# PicoPrint-Motors.net
KiCad netlist of a schematic drawn in Altium Designer
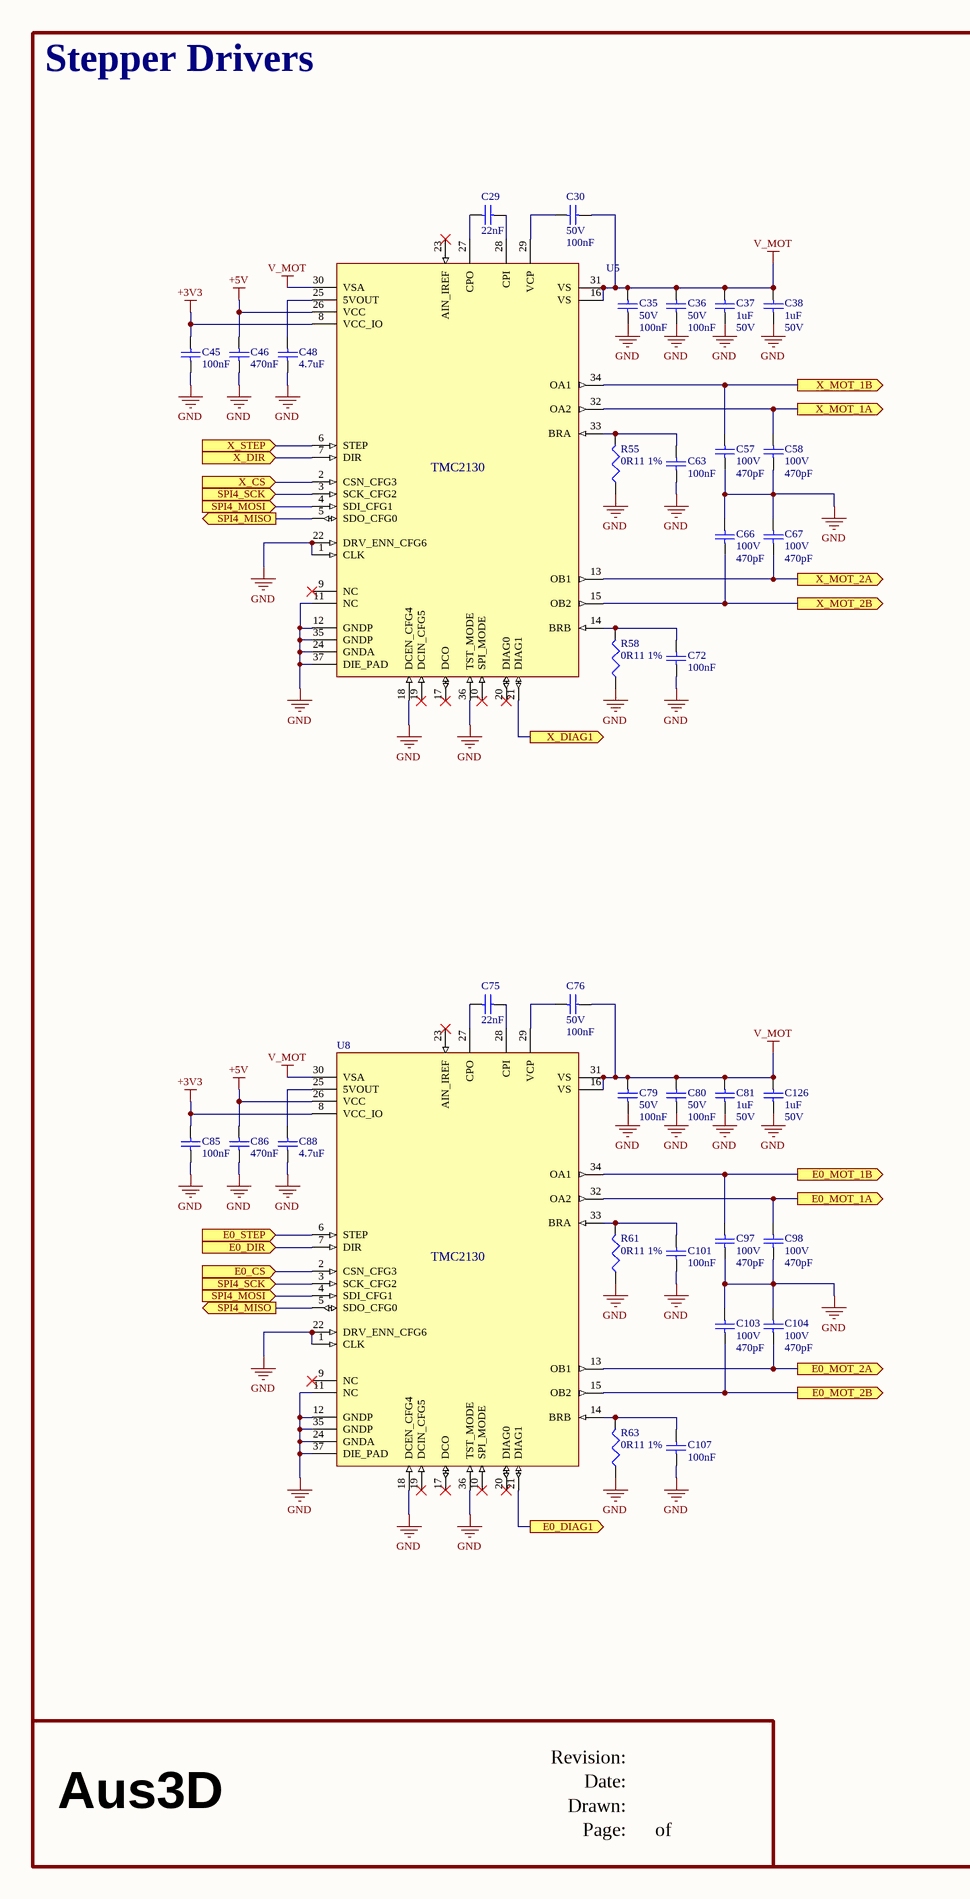
[diagram p0: PicoPrint-Motors.SchDoc, left]
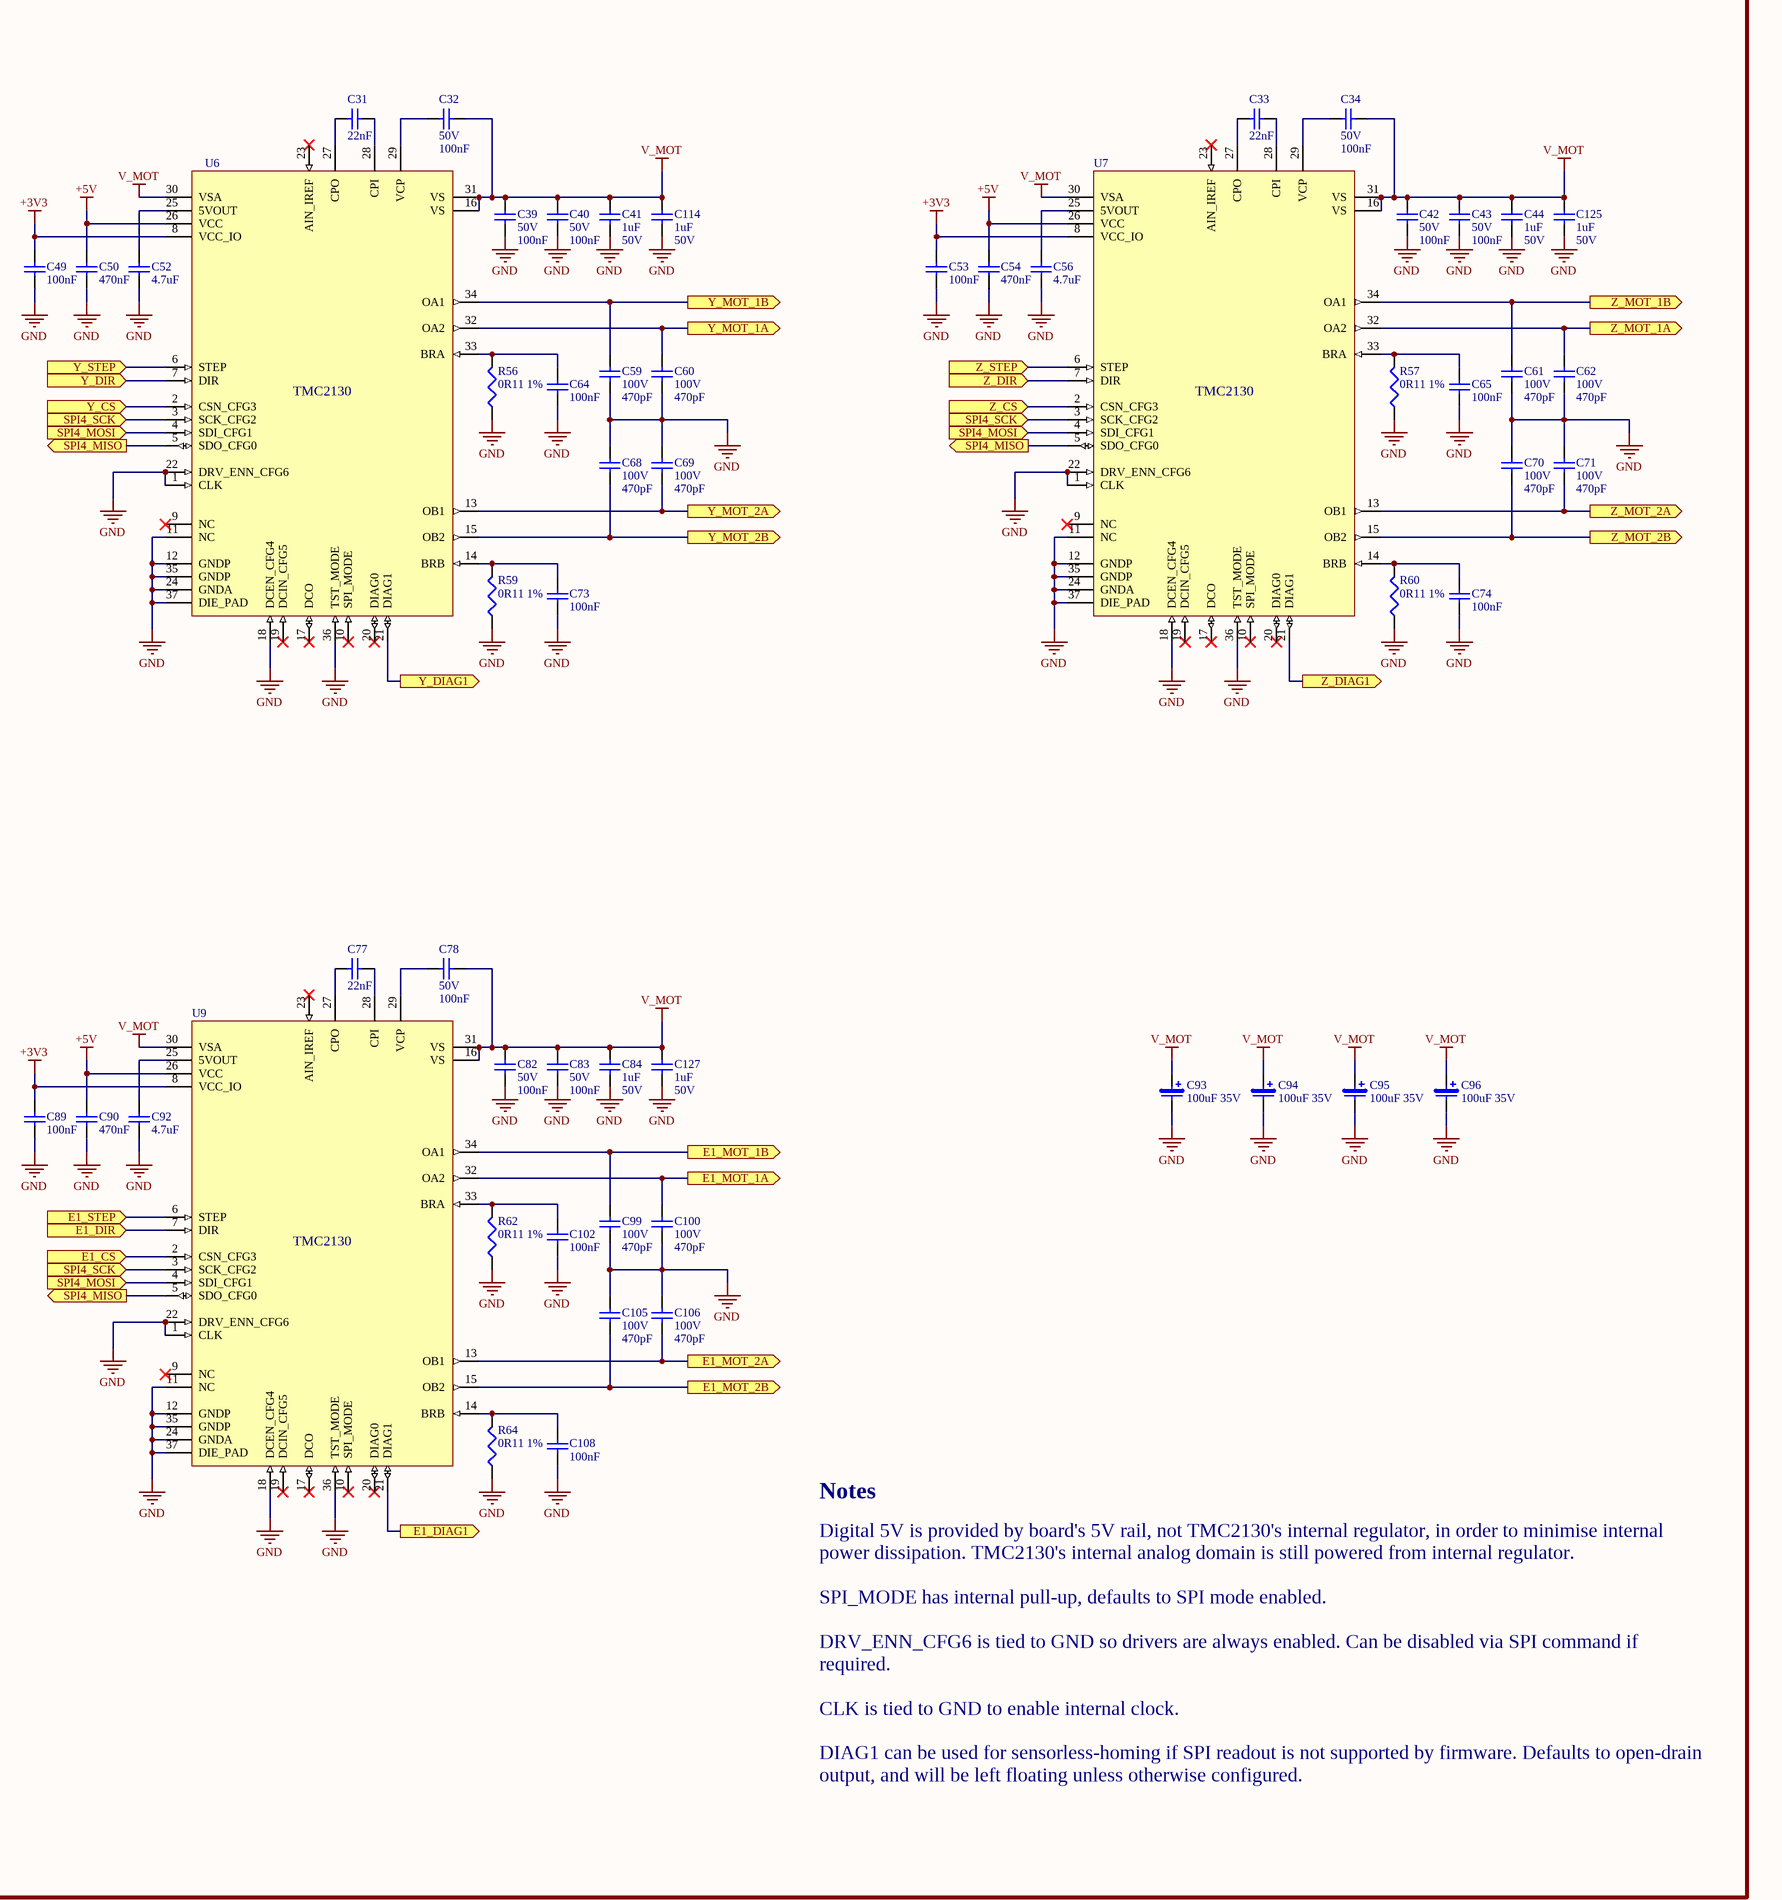
[diagram p1: PicoPrint-Motors.SchDoc, right]

(export (version "E")
  (design (tool "Eeschema 10.0.6"))
  (components
    (comp (ref "C29")
      (value "22nF")
      (footprint "CAP 1005-0402")
      (description "Capacitor (SMD Ceramic)")
      (fields
        (field (name "VOLTAGE") "50V")
        (field (name "Comment") "CapC-0402-22nF-50V")
        (field (name "PUBLISHER") "Altium Limited")
      )
      (libsource (lib "picoprint_library") (part "CapC-0402-22nF-50V"))
    )
    (comp (ref "C30")
      (value "100nF")
      (footprint "CAP 1005-0402")
      (description "Capacitor (SMD Ceramic)")
      (fields
        (field (name "VOLTAGE") "50V")
        (field (name "Comment") "CapC-0402-100nF-50V")
        (field (name "PUBLISHER") "Altium Limited")
      )
      (libsource (lib "picoprint_library") (part "CapC-0402-100nF-50V"))
    )
    (comp (ref "C31")
      (value "22nF")
      (footprint "CAP 1005-0402")
      (description "Capacitor (SMD Ceramic)")
      (fields
        (field (name "VOLTAGE") "50V")
        (field (name "Comment") "CapC-0402-22nF-50V")
        (field (name "PUBLISHER") "Altium Limited")
      )
      (libsource (lib "picoprint_library") (part "CapC-0402-22nF-50V"))
    )
    (comp (ref "C32")
      (value "100nF")
      (footprint "CAP 1005-0402")
      (description "Capacitor (SMD Ceramic)")
      (fields
        (field (name "VOLTAGE") "50V")
        (field (name "Comment") "CapC-0402-100nF-50V")
        (field (name "PUBLISHER") "Altium Limited")
      )
      (libsource (lib "picoprint_library") (part "CapC-0402-100nF-50V"))
    )
    (comp (ref "C33")
      (value "22nF")
      (footprint "CAP 1005-0402")
      (description "Capacitor (SMD Ceramic)")
      (fields
        (field (name "VOLTAGE") "50V")
        (field (name "Comment") "CapC-0402-22nF-50V")
        (field (name "PUBLISHER") "Altium Limited")
      )
      (libsource (lib "picoprint_library") (part "CapC-0402-22nF-50V"))
    )
    (comp (ref "C34")
      (value "100nF")
      (footprint "CAP 1005-0402")
      (description "Capacitor (SMD Ceramic)")
      (fields
        (field (name "VOLTAGE") "50V")
        (field (name "Comment") "CapC-0402-100nF-50V")
        (field (name "PUBLISHER") "Altium Limited")
      )
      (libsource (lib "picoprint_library") (part "CapC-0402-100nF-50V"))
    )
    (comp (ref "C35")
      (value "100nF")
      (footprint "CAP 1005-0402")
      (description "Capacitor (SMD Ceramic)")
      (fields
        (field (name "VOLTAGE") "50V")
        (field (name "Comment") "CapC-0402-100nF-50V")
        (field (name "PUBLISHER") "Altium Limited")
      )
      (libsource (lib "picoprint_library") (part "CapC-0402-100nF-50V"))
    )
    (comp (ref "C36")
      (value "100nF")
      (footprint "CAP 1005-0402")
      (description "Capacitor (SMD Ceramic)")
      (fields
        (field (name "VOLTAGE") "50V")
        (field (name "Comment") "CapC-0402-100nF-50V")
        (field (name "PUBLISHER") "Altium Limited")
      )
      (libsource (lib "picoprint_library") (part "CapC-0402-100nF-50V"))
    )
    (comp (ref "C37")
      (value "1uF")
      (footprint "Cap 1608-0603")
      (description "Capacitor (SMD Ceramic)")
      (fields
        (field (name "VOLTAGE") "50V")
        (field (name "Comment") "CapC-0603-1uF 50V")
        (field (name "PUBLISHER") "Altium Limited")
      )
      (libsource (lib "picoprint_library") (part "CapC-0603-1uF 50V"))
    )
    (comp (ref "C38")
      (value "1uF")
      (footprint "Cap 1608-0603")
      (description "Capacitor (SMD Ceramic)")
      (fields
        (field (name "VOLTAGE") "50V")
        (field (name "Comment") "CapC-0603-1uF 50V")
        (field (name "PUBLISHER") "Altium Limited")
      )
      (libsource (lib "picoprint_library") (part "CapC-0603-1uF 50V"))
    )
    (comp (ref "C39")
      (value "100nF")
      (footprint "CAP 1005-0402")
      (description "Capacitor (SMD Ceramic)")
      (fields
        (field (name "VOLTAGE") "50V")
        (field (name "Comment") "CapC-0402-100nF-50V")
        (field (name "PUBLISHER") "Altium Limited")
      )
      (libsource (lib "picoprint_library") (part "CapC-0402-100nF-50V"))
    )
    (comp (ref "C40")
      (value "100nF")
      (footprint "CAP 1005-0402")
      (description "Capacitor (SMD Ceramic)")
      (fields
        (field (name "VOLTAGE") "50V")
        (field (name "Comment") "CapC-0402-100nF-50V")
        (field (name "PUBLISHER") "Altium Limited")
      )
      (libsource (lib "picoprint_library") (part "CapC-0402-100nF-50V"))
    )
    (comp (ref "C41")
      (value "1uF")
      (footprint "Cap 1608-0603")
      (description "Capacitor (SMD Ceramic)")
      (fields
        (field (name "VOLTAGE") "50V")
        (field (name "Comment") "CapC-0603-1uF 50V")
        (field (name "PUBLISHER") "Altium Limited")
      )
      (libsource (lib "picoprint_library") (part "CapC-0603-1uF 50V"))
    )
    (comp (ref "C42")
      (value "100nF")
      (footprint "CAP 1005-0402")
      (description "Capacitor (SMD Ceramic)")
      (fields
        (field (name "VOLTAGE") "50V")
        (field (name "Comment") "CapC-0402-100nF-50V")
        (field (name "PUBLISHER") "Altium Limited")
      )
      (libsource (lib "picoprint_library") (part "CapC-0402-100nF-50V"))
    )
    (comp (ref "C43")
      (value "100nF")
      (footprint "CAP 1005-0402")
      (description "Capacitor (SMD Ceramic)")
      (fields
        (field (name "VOLTAGE") "50V")
        (field (name "Comment") "CapC-0402-100nF-50V")
        (field (name "PUBLISHER") "Altium Limited")
      )
      (libsource (lib "picoprint_library") (part "CapC-0402-100nF-50V"))
    )
    (comp (ref "C44")
      (value "1uF")
      (footprint "Cap 1608-0603")
      (description "Capacitor (SMD Ceramic)")
      (fields
        (field (name "VOLTAGE") "50V")
        (field (name "Comment") "CapC-0603-1uF 50V")
        (field (name "PUBLISHER") "Altium Limited")
      )
      (libsource (lib "picoprint_library") (part "CapC-0603-1uF 50V"))
    )
    (comp (ref "C45")
      (value "100nF")
      (footprint "CAP 1005-0402")
      (description "Capacitor (SMD Ceramic)")
      (fields (field (name "Comment") "CapC-0402-100nF") (field (name "PUBLISHER") "Altium Limited"))
      (libsource (lib "picoprint_library") (part "CapC-0402-100nF"))
    )
    (comp (ref "C46")
      (value "470nF")
      (footprint "CAP 1005-0402")
      (description "Capacitor (SMD Ceramic)")
      (fields (field (name "Comment") "CapC-0402-470nF") (field (name "PUBLISHER") "Altium Limited"))
      (libsource (lib "picoprint_library") (part "CapC-0402-470nF"))
    )
    (comp (ref "C48")
      (value "4.7uF")
      (footprint "CAP 1005-0402")
      (description "Capacitor (SMD Ceramic)")
      (fields
        (field (name "VOLTAGE") "10V")
        (field (name "Comment") "CapC-0402-4.7uF-10V")
        (field (name "PUBLISHER") "Altium Limited")
      )
      (libsource (lib "picoprint_library") (part "CapC-0402-4.7uF-10V"))
    )
    (comp (ref "C49")
      (value "100nF")
      (footprint "CAP 1005-0402")
      (description "Capacitor (SMD Ceramic)")
      (fields (field (name "Comment") "CapC-0402-100nF") (field (name "PUBLISHER") "Altium Limited"))
      (libsource (lib "picoprint_library") (part "CapC-0402-100nF"))
    )
    (comp (ref "C50")
      (value "470nF")
      (footprint "CAP 1005-0402")
      (description "Capacitor (SMD Ceramic)")
      (fields (field (name "Comment") "CapC-0402-470nF") (field (name "PUBLISHER") "Altium Limited"))
      (libsource (lib "picoprint_library") (part "CapC-0402-470nF"))
    )
    (comp (ref "C52")
      (value "4.7uF")
      (footprint "CAP 1005-0402")
      (description "Capacitor (SMD Ceramic)")
      (fields
        (field (name "VOLTAGE") "10V")
        (field (name "Comment") "CapC-0402-4.7uF-10V")
        (field (name "PUBLISHER") "Altium Limited")
      )
      (libsource (lib "picoprint_library") (part "CapC-0402-4.7uF-10V"))
    )
    (comp (ref "C53")
      (value "100nF")
      (footprint "CAP 1005-0402")
      (description "Capacitor (SMD Ceramic)")
      (fields (field (name "Comment") "CapC-0402-100nF") (field (name "PUBLISHER") "Altium Limited"))
      (libsource (lib "picoprint_library") (part "CapC-0402-100nF"))
    )
    (comp (ref "C54")
      (value "470nF")
      (footprint "CAP 1005-0402")
      (description "Capacitor (SMD Ceramic)")
      (fields (field (name "Comment") "CapC-0402-470nF") (field (name "PUBLISHER") "Altium Limited"))
      (libsource (lib "picoprint_library") (part "CapC-0402-470nF"))
    )
    (comp (ref "C56")
      (value "4.7uF")
      (footprint "CAP 1005-0402")
      (description "Capacitor (SMD Ceramic)")
      (fields
        (field (name "VOLTAGE") "10V")
        (field (name "Comment") "CapC-0402-4.7uF-10V")
        (field (name "PUBLISHER") "Altium Limited")
      )
      (libsource (lib "picoprint_library") (part "CapC-0402-4.7uF-10V"))
    )
    (comp (ref "C57")
      (value "470pF")
      (footprint "CAP 1005-0402")
      (description "Capacitor (SMD Ceramic)")
      (fields
        (field (name "VOLTAGE") "100V")
        (field (name "Comment") "CapC-0402-470pF-100V")
        (field (name "PUBLISHER") "Altium Limited")
      )
      (libsource (lib "picoprint_library") (part "CapC-0402-470pF-100V"))
    )
    (comp (ref "C58")
      (value "470pF")
      (footprint "CAP 1005-0402")
      (description "Capacitor (SMD Ceramic)")
      (fields
        (field (name "VOLTAGE") "100V")
        (field (name "Comment") "CapC-0402-470pF-100V")
        (field (name "PUBLISHER") "Altium Limited")
      )
      (libsource (lib "picoprint_library") (part "CapC-0402-470pF-100V"))
    )
    (comp (ref "C59")
      (value "470pF")
      (footprint "CAP 1005-0402")
      (description "Capacitor (SMD Ceramic)")
      (fields
        (field (name "VOLTAGE") "100V")
        (field (name "Comment") "CapC-0402-470pF-100V")
        (field (name "PUBLISHER") "Altium Limited")
      )
      (libsource (lib "picoprint_library") (part "CapC-0402-470pF-100V"))
    )
    (comp (ref "C60")
      (value "470pF")
      (footprint "CAP 1005-0402")
      (description "Capacitor (SMD Ceramic)")
      (fields
        (field (name "VOLTAGE") "100V")
        (field (name "Comment") "CapC-0402-470pF-100V")
        (field (name "PUBLISHER") "Altium Limited")
      )
      (libsource (lib "picoprint_library") (part "CapC-0402-470pF-100V"))
    )
    (comp (ref "C61")
      (value "470pF")
      (footprint "CAP 1005-0402")
      (description "Capacitor (SMD Ceramic)")
      (fields
        (field (name "VOLTAGE") "100V")
        (field (name "Comment") "CapC-0402-470pF-100V")
        (field (name "PUBLISHER") "Altium Limited")
      )
      (libsource (lib "picoprint_library") (part "CapC-0402-470pF-100V"))
    )
    (comp (ref "C62")
      (value "470pF")
      (footprint "CAP 1005-0402")
      (description "Capacitor (SMD Ceramic)")
      (fields
        (field (name "VOLTAGE") "100V")
        (field (name "Comment") "CapC-0402-470pF-100V")
        (field (name "PUBLISHER") "Altium Limited")
      )
      (libsource (lib "picoprint_library") (part "CapC-0402-470pF-100V"))
    )
    (comp (ref "C63")
      (value "100nF")
      (footprint "CAP 1005-0402")
      (description "Capacitor (SMD Ceramic)")
      (fields (field (name "Comment") "CapC-0402-100nF") (field (name "PUBLISHER") "Altium Limited"))
      (libsource (lib "picoprint_library") (part "CapC-0402-100nF"))
    )
    (comp (ref "C64")
      (value "100nF")
      (footprint "CAP 1005-0402")
      (description "Capacitor (SMD Ceramic)")
      (fields (field (name "Comment") "CapC-0402-100nF") (field (name "PUBLISHER") "Altium Limited"))
      (libsource (lib "picoprint_library") (part "CapC-0402-100nF"))
    )
    (comp (ref "C65")
      (value "100nF")
      (footprint "CAP 1005-0402")
      (description "Capacitor (SMD Ceramic)")
      (fields (field (name "Comment") "CapC-0402-100nF") (field (name "PUBLISHER") "Altium Limited"))
      (libsource (lib "picoprint_library") (part "CapC-0402-100nF"))
    )
    (comp (ref "C66")
      (value "470pF")
      (footprint "CAP 1005-0402")
      (description "Capacitor (SMD Ceramic)")
      (fields
        (field (name "VOLTAGE") "100V")
        (field (name "Comment") "CapC-0402-470pF-100V")
        (field (name "PUBLISHER") "Altium Limited")
      )
      (libsource (lib "picoprint_library") (part "CapC-0402-470pF-100V"))
    )
    (comp (ref "C67")
      (value "470pF")
      (footprint "CAP 1005-0402")
      (description "Capacitor (SMD Ceramic)")
      (fields
        (field (name "VOLTAGE") "100V")
        (field (name "Comment") "CapC-0402-470pF-100V")
        (field (name "PUBLISHER") "Altium Limited")
      )
      (libsource (lib "picoprint_library") (part "CapC-0402-470pF-100V"))
    )
    (comp (ref "C68")
      (value "470pF")
      (footprint "CAP 1005-0402")
      (description "Capacitor (SMD Ceramic)")
      (fields
        (field (name "VOLTAGE") "100V")
        (field (name "Comment") "CapC-0402-470pF-100V")
        (field (name "PUBLISHER") "Altium Limited")
      )
      (libsource (lib "picoprint_library") (part "CapC-0402-470pF-100V"))
    )
    (comp (ref "C69")
      (value "470pF")
      (footprint "CAP 1005-0402")
      (description "Capacitor (SMD Ceramic)")
      (fields
        (field (name "VOLTAGE") "100V")
        (field (name "Comment") "CapC-0402-470pF-100V")
        (field (name "PUBLISHER") "Altium Limited")
      )
      (libsource (lib "picoprint_library") (part "CapC-0402-470pF-100V"))
    )
    (comp (ref "C70")
      (value "470pF")
      (footprint "CAP 1005-0402")
      (description "Capacitor (SMD Ceramic)")
      (fields
        (field (name "VOLTAGE") "100V")
        (field (name "Comment") "CapC-0402-470pF-100V")
        (field (name "PUBLISHER") "Altium Limited")
      )
      (libsource (lib "picoprint_library") (part "CapC-0402-470pF-100V"))
    )
    (comp (ref "C71")
      (value "470pF")
      (footprint "CAP 1005-0402")
      (description "Capacitor (SMD Ceramic)")
      (fields
        (field (name "VOLTAGE") "100V")
        (field (name "Comment") "CapC-0402-470pF-100V")
        (field (name "PUBLISHER") "Altium Limited")
      )
      (libsource (lib "picoprint_library") (part "CapC-0402-470pF-100V"))
    )
    (comp (ref "C72")
      (value "100nF")
      (footprint "CAP 1005-0402")
      (description "Capacitor (SMD Ceramic)")
      (fields (field (name "Comment") "CapC-0402-100nF") (field (name "PUBLISHER") "Altium Limited"))
      (libsource (lib "picoprint_library") (part "CapC-0402-100nF"))
    )
    (comp (ref "C73")
      (value "100nF")
      (footprint "CAP 1005-0402")
      (description "Capacitor (SMD Ceramic)")
      (fields (field (name "Comment") "CapC-0402-100nF") (field (name "PUBLISHER") "Altium Limited"))
      (libsource (lib "picoprint_library") (part "CapC-0402-100nF"))
    )
    (comp (ref "C74")
      (value "100nF")
      (footprint "CAP 1005-0402")
      (description "Capacitor (SMD Ceramic)")
      (fields (field (name "Comment") "CapC-0402-100nF") (field (name "PUBLISHER") "Altium Limited"))
      (libsource (lib "picoprint_library") (part "CapC-0402-100nF"))
    )
    (comp (ref "C75")
      (value "22nF")
      (footprint "CAP 1005-0402")
      (description "Capacitor (SMD Ceramic)")
      (fields
        (field (name "VOLTAGE") "50V")
        (field (name "Comment") "CapC-0402-22nF-50V")
        (field (name "PUBLISHER") "Altium Limited")
      )
      (libsource (lib "picoprint_library") (part "CapC-0402-22nF-50V"))
    )
    (comp (ref "C76")
      (value "100nF")
      (footprint "CAP 1005-0402")
      (description "Capacitor (SMD Ceramic)")
      (fields
        (field (name "VOLTAGE") "50V")
        (field (name "Comment") "CapC-0402-100nF-50V")
        (field (name "PUBLISHER") "Altium Limited")
      )
      (libsource (lib "picoprint_library") (part "CapC-0402-100nF-50V"))
    )
    (comp (ref "C77")
      (value "22nF")
      (footprint "CAP 1005-0402")
      (description "Capacitor (SMD Ceramic)")
      (fields
        (field (name "VOLTAGE") "50V")
        (field (name "Comment") "CapC-0402-22nF-50V")
        (field (name "PUBLISHER") "Altium Limited")
      )
      (libsource (lib "picoprint_library") (part "CapC-0402-22nF-50V"))
    )
    (comp (ref "C78")
      (value "100nF")
      (footprint "CAP 1005-0402")
      (description "Capacitor (SMD Ceramic)")
      (fields
        (field (name "VOLTAGE") "50V")
        (field (name "Comment") "CapC-0402-100nF-50V")
        (field (name "PUBLISHER") "Altium Limited")
      )
      (libsource (lib "picoprint_library") (part "CapC-0402-100nF-50V"))
    )
    (comp (ref "C79")
      (value "100nF")
      (footprint "CAP 1005-0402")
      (description "Capacitor (SMD Ceramic)")
      (fields
        (field (name "VOLTAGE") "50V")
        (field (name "Comment") "CapC-0402-100nF-50V")
        (field (name "PUBLISHER") "Altium Limited")
      )
      (libsource (lib "picoprint_library") (part "CapC-0402-100nF-50V"))
    )
    (comp (ref "C80")
      (value "100nF")
      (footprint "CAP 1005-0402")
      (description "Capacitor (SMD Ceramic)")
      (fields
        (field (name "VOLTAGE") "50V")
        (field (name "Comment") "CapC-0402-100nF-50V")
        (field (name "PUBLISHER") "Altium Limited")
      )
      (libsource (lib "picoprint_library") (part "CapC-0402-100nF-50V"))
    )
    (comp (ref "C81")
      (value "1uF")
      (footprint "Cap 1608-0603")
      (description "Capacitor (SMD Ceramic)")
      (fields
        (field (name "VOLTAGE") "50V")
        (field (name "Comment") "CapC-0603-1uF 50V")
        (field (name "PUBLISHER") "Altium Limited")
      )
      (libsource (lib "picoprint_library") (part "CapC-0603-1uF 50V"))
    )
    (comp (ref "C82")
      (value "100nF")
      (footprint "CAP 1005-0402")
      (description "Capacitor (SMD Ceramic)")
      (fields
        (field (name "VOLTAGE") "50V")
        (field (name "Comment") "CapC-0402-100nF-50V")
        (field (name "PUBLISHER") "Altium Limited")
      )
      (libsource (lib "picoprint_library") (part "CapC-0402-100nF-50V"))
    )
    (comp (ref "C83")
      (value "100nF")
      (footprint "CAP 1005-0402")
      (description "Capacitor (SMD Ceramic)")
      (fields
        (field (name "VOLTAGE") "50V")
        (field (name "Comment") "CapC-0402-100nF-50V")
        (field (name "PUBLISHER") "Altium Limited")
      )
      (libsource (lib "picoprint_library") (part "CapC-0402-100nF-50V"))
    )
    (comp (ref "C84")
      (value "1uF")
      (footprint "Cap 1608-0603")
      (description "Capacitor (SMD Ceramic)")
      (fields
        (field (name "VOLTAGE") "50V")
        (field (name "Comment") "CapC-0603-1uF 50V")
        (field (name "PUBLISHER") "Altium Limited")
      )
      (libsource (lib "picoprint_library") (part "CapC-0603-1uF 50V"))
    )
    (comp (ref "C85")
      (value "100nF")
      (footprint "CAP 1005-0402")
      (description "Capacitor (SMD Ceramic)")
      (fields (field (name "Comment") "CapC-0402-100nF") (field (name "PUBLISHER") "Altium Limited"))
      (libsource (lib "picoprint_library") (part "CapC-0402-100nF"))
    )
    (comp (ref "C86")
      (value "470nF")
      (footprint "CAP 1005-0402")
      (description "Capacitor (SMD Ceramic)")
      (fields (field (name "Comment") "CapC-0402-470nF") (field (name "PUBLISHER") "Altium Limited"))
      (libsource (lib "picoprint_library") (part "CapC-0402-470nF"))
    )
    (comp (ref "C88")
      (value "4.7uF")
      (footprint "CAP 1005-0402")
      (description "Capacitor (SMD Ceramic)")
      (fields
        (field (name "VOLTAGE") "10V")
        (field (name "Comment") "CapC-0402-4.7uF-10V")
        (field (name "PUBLISHER") "Altium Limited")
      )
      (libsource (lib "picoprint_library") (part "CapC-0402-4.7uF-10V"))
    )
    (comp (ref "C89")
      (value "100nF")
      (footprint "CAP 1005-0402")
      (description "Capacitor (SMD Ceramic)")
      (fields (field (name "Comment") "CapC-0402-100nF") (field (name "PUBLISHER") "Altium Limited"))
      (libsource (lib "picoprint_library") (part "CapC-0402-100nF"))
    )
    (comp (ref "C90")
      (value "470nF")
      (footprint "CAP 1005-0402")
      (description "Capacitor (SMD Ceramic)")
      (fields (field (name "Comment") "CapC-0402-470nF") (field (name "PUBLISHER") "Altium Limited"))
      (libsource (lib "picoprint_library") (part "CapC-0402-470nF"))
    )
    (comp (ref "C92")
      (value "4.7uF")
      (footprint "CAP 1005-0402")
      (description "Capacitor (SMD Ceramic)")
      (fields
        (field (name "VOLTAGE") "10V")
        (field (name "Comment") "CapC-0402-4.7uF-10V")
        (field (name "PUBLISHER") "Altium Limited")
      )
      (libsource (lib "picoprint_library") (part "CapC-0402-4.7uF-10V"))
    )
    (comp (ref "C93")
      (value "100uF 35V")
      (footprint "CAP EL PANASONIC")
      (description "Capacitor (SMD Polarised Electrolytic)")
      (fields (field (name "Comment") "CapE-6.3-100uF-35V") (field (name "PUBLISHER") "Altium Limited"))
      (libsource (lib "picoprint_library") (part "CapE-6.3-100uF-35V"))
    )
    (comp (ref "C94")
      (value "100uF 35V")
      (footprint "CAP EL PANASONIC")
      (description "Capacitor (SMD Polarised Electrolytic)")
      (fields (field (name "Comment") "CapE-6.3-100uF-35V") (field (name "PUBLISHER") "Altium Limited"))
      (libsource (lib "picoprint_library") (part "CapE-6.3-100uF-35V"))
    )
    (comp (ref "C95")
      (value "100uF 35V")
      (footprint "CAP EL PANASONIC")
      (description "Capacitor (SMD Polarised Electrolytic)")
      (fields (field (name "Comment") "CapE-6.3-100uF-35V") (field (name "PUBLISHER") "Altium Limited"))
      (libsource (lib "picoprint_library") (part "CapE-6.3-100uF-35V"))
    )
    (comp (ref "C96")
      (value "100uF 35V")
      (footprint "CAP EL PANASONIC")
      (description "Capacitor (SMD Polarised Electrolytic)")
      (fields (field (name "Comment") "CapE-6.3-100uF-35V") (field (name "PUBLISHER") "Altium Limited"))
      (libsource (lib "picoprint_library") (part "CapE-6.3-100uF-35V"))
    )
    (comp (ref "C97")
      (value "470pF")
      (footprint "CAP 1005-0402")
      (description "Capacitor (SMD Ceramic)")
      (fields
        (field (name "VOLTAGE") "100V")
        (field (name "Comment") "CapC-0402-470pF-100V")
        (field (name "PUBLISHER") "Altium Limited")
      )
      (libsource (lib "picoprint_library") (part "CapC-0402-470pF-100V"))
    )
    (comp (ref "C98")
      (value "470pF")
      (footprint "CAP 1005-0402")
      (description "Capacitor (SMD Ceramic)")
      (fields
        (field (name "VOLTAGE") "100V")
        (field (name "Comment") "CapC-0402-470pF-100V")
        (field (name "PUBLISHER") "Altium Limited")
      )
      (libsource (lib "picoprint_library") (part "CapC-0402-470pF-100V"))
    )
    (comp (ref "C99")
      (value "470pF")
      (footprint "CAP 1005-0402")
      (description "Capacitor (SMD Ceramic)")
      (fields
        (field (name "VOLTAGE") "100V")
        (field (name "Comment") "CapC-0402-470pF-100V")
        (field (name "PUBLISHER") "Altium Limited")
      )
      (libsource (lib "picoprint_library") (part "CapC-0402-470pF-100V"))
    )
    (comp (ref "C100")
      (value "470pF")
      (footprint "CAP 1005-0402")
      (description "Capacitor (SMD Ceramic)")
      (fields
        (field (name "VOLTAGE") "100V")
        (field (name "Comment") "CapC-0402-470pF-100V")
        (field (name "PUBLISHER") "Altium Limited")
      )
      (libsource (lib "picoprint_library") (part "CapC-0402-470pF-100V"))
    )
    (comp (ref "C101")
      (value "100nF")
      (footprint "CAP 1005-0402")
      (description "Capacitor (SMD Ceramic)")
      (fields (field (name "Comment") "CapC-0402-100nF") (field (name "PUBLISHER") "Altium Limited"))
      (libsource (lib "picoprint_library") (part "CapC-0402-100nF"))
    )
    (comp (ref "C102")
      (value "100nF")
      (footprint "CAP 1005-0402")
      (description "Capacitor (SMD Ceramic)")
      (fields (field (name "Comment") "CapC-0402-100nF") (field (name "PUBLISHER") "Altium Limited"))
      (libsource (lib "picoprint_library") (part "CapC-0402-100nF"))
    )
    (comp (ref "C103")
      (value "470pF")
      (footprint "CAP 1005-0402")
      (description "Capacitor (SMD Ceramic)")
      (fields
        (field (name "VOLTAGE") "100V")
        (field (name "Comment") "CapC-0402-470pF-100V")
        (field (name "PUBLISHER") "Altium Limited")
      )
      (libsource (lib "picoprint_library") (part "CapC-0402-470pF-100V"))
    )
    (comp (ref "C104")
      (value "470pF")
      (footprint "CAP 1005-0402")
      (description "Capacitor (SMD Ceramic)")
      (fields
        (field (name "VOLTAGE") "100V")
        (field (name "Comment") "CapC-0402-470pF-100V")
        (field (name "PUBLISHER") "Altium Limited")
      )
      (libsource (lib "picoprint_library") (part "CapC-0402-470pF-100V"))
    )
    (comp (ref "C105")
      (value "470pF")
      (footprint "CAP 1005-0402")
      (description "Capacitor (SMD Ceramic)")
      (fields
        (field (name "VOLTAGE") "100V")
        (field (name "Comment") "CapC-0402-470pF-100V")
        (field (name "PUBLISHER") "Altium Limited")
      )
      (libsource (lib "picoprint_library") (part "CapC-0402-470pF-100V"))
    )
    (comp (ref "C106")
      (value "470pF")
      (footprint "CAP 1005-0402")
      (description "Capacitor (SMD Ceramic)")
      (fields
        (field (name "VOLTAGE") "100V")
        (field (name "Comment") "CapC-0402-470pF-100V")
        (field (name "PUBLISHER") "Altium Limited")
      )
      (libsource (lib "picoprint_library") (part "CapC-0402-470pF-100V"))
    )
    (comp (ref "C107")
      (value "100nF")
      (footprint "CAP 1005-0402")
      (description "Capacitor (SMD Ceramic)")
      (fields (field (name "Comment") "CapC-0402-100nF") (field (name "PUBLISHER") "Altium Limited"))
      (libsource (lib "picoprint_library") (part "CapC-0402-100nF"))
    )
    (comp (ref "C108")
      (value "100nF")
      (footprint "CAP 1005-0402")
      (description "Capacitor (SMD Ceramic)")
      (fields (field (name "Comment") "CapC-0402-100nF") (field (name "PUBLISHER") "Altium Limited"))
      (libsource (lib "picoprint_library") (part "CapC-0402-100nF"))
    )
    (comp (ref "C114")
      (value "1uF")
      (footprint "Cap 1608-0603")
      (description "Capacitor (SMD Ceramic)")
      (fields
        (field (name "VOLTAGE") "50V")
        (field (name "Comment") "CapC-0603-1uF 50V")
        (field (name "PUBLISHER") "Altium Limited")
      )
      (libsource (lib "picoprint_library") (part "CapC-0603-1uF 50V"))
    )
    (comp (ref "C125")
      (value "1uF")
      (footprint "Cap 1608-0603")
      (description "Capacitor (SMD Ceramic)")
      (fields
        (field (name "VOLTAGE") "50V")
        (field (name "Comment") "CapC-0603-1uF 50V")
        (field (name "PUBLISHER") "Altium Limited")
      )
      (libsource (lib "picoprint_library") (part "CapC-0603-1uF 50V"))
    )
    (comp (ref "C126")
      (value "1uF")
      (footprint "Cap 1608-0603")
      (description "Capacitor (SMD Ceramic)")
      (fields
        (field (name "VOLTAGE") "50V")
        (field (name "Comment") "CapC-0603-1uF 50V")
        (field (name "PUBLISHER") "Altium Limited")
      )
      (libsource (lib "picoprint_library") (part "CapC-0603-1uF 50V"))
    )
    (comp (ref "C127")
      (value "1uF")
      (footprint "Cap 1608-0603")
      (description "Capacitor (SMD Ceramic)")
      (fields
        (field (name "VOLTAGE") "50V")
        (field (name "Comment") "CapC-0603-1uF 50V")
        (field (name "PUBLISHER") "Altium Limited")
      )
      (libsource (lib "picoprint_library") (part "CapC-0603-1uF 50V"))
    )
    (comp (ref "R55")
      (value "0R11 1%")
      (footprint "Res 2012-0805")
      (description "Resistor")
      (fields (field (name "Comment") "Res-0805-0R11-0.333W") (field (name "PUBLISHER") "Altium Limited"))
      (libsource (lib "picoprint_library") (part "Res-0805-0R11"))
    )
    (comp (ref "R56")
      (value "0R11 1%")
      (footprint "Res 2012-0805")
      (description "Resistor")
      (fields (field (name "Comment") "Res-0805-0R11-0.333W") (field (name "PUBLISHER") "Altium Limited"))
      (libsource (lib "picoprint_library") (part "Res-0805-0R11"))
    )
    (comp (ref "R57")
      (value "0R11 1%")
      (footprint "Res 2012-0805")
      (description "Resistor")
      (fields (field (name "Comment") "Res-0805-0R11-0.333W") (field (name "PUBLISHER") "Altium Limited"))
      (libsource (lib "picoprint_library") (part "Res-0805-0R11"))
    )
    (comp (ref "R58")
      (value "0R11 1%")
      (footprint "Res 2012-0805")
      (description "Resistor")
      (fields (field (name "Comment") "Res-0805-0R11-0.333W") (field (name "PUBLISHER") "Altium Limited"))
      (libsource (lib "picoprint_library") (part "Res-0805-0R11"))
    )
    (comp (ref "R59")
      (value "0R11 1%")
      (footprint "Res 2012-0805")
      (description "Resistor")
      (fields (field (name "Comment") "Res-0805-0R11-0.333W") (field (name "PUBLISHER") "Altium Limited"))
      (libsource (lib "picoprint_library") (part "Res-0805-0R11"))
    )
    (comp (ref "R60")
      (value "0R11 1%")
      (footprint "Res 2012-0805")
      (description "Resistor")
      (fields (field (name "Comment") "Res-0805-0R11-0.333W") (field (name "PUBLISHER") "Altium Limited"))
      (libsource (lib "picoprint_library") (part "Res-0805-0R11"))
    )
    (comp (ref "R61")
      (value "0R11 1%")
      (footprint "Res 2012-0805")
      (description "Resistor")
      (fields (field (name "Comment") "Res-0805-0R11-0.333W") (field (name "PUBLISHER") "Altium Limited"))
      (libsource (lib "picoprint_library") (part "Res-0805-0R11"))
    )
    (comp (ref "R62")
      (value "0R11 1%")
      (footprint "Res 2012-0805")
      (description "Resistor")
      (fields (field (name "Comment") "Res-0805-0R11-0.333W") (field (name "PUBLISHER") "Altium Limited"))
      (libsource (lib "picoprint_library") (part "Res-0805-0R11"))
    )
    (comp (ref "R63")
      (value "0R11 1%")
      (footprint "Res 2012-0805")
      (description "Resistor")
      (fields (field (name "Comment") "Res-0805-0R11-0.333W") (field (name "PUBLISHER") "Altium Limited"))
      (libsource (lib "picoprint_library") (part "Res-0805-0R11"))
    )
    (comp (ref "R64")
      (value "0R11 1%")
      (footprint "Res 2012-0805")
      (description "Resistor")
      (fields (field (name "Comment") "Res-0805-0R11-0.333W") (field (name "PUBLISHER") "Altium Limited"))
      (libsource (lib "picoprint_library") (part "Res-0805-0R11"))
    )
    (comp (ref "U5")
      (value "TMC2130-LA")
      (footprint "QFN50P500X600X90_HS-37N")
      (description "Stepper Driver IC")
      (libsource (lib "picoprint_library") (part "TMC2130_LA"))
    )
    (comp (ref "U6")
      (value "TMC2130-LA")
      (footprint "QFN50P500X600X90_HS-37N")
      (description "Stepper Driver IC")
      (libsource (lib "picoprint_library") (part "TMC2130_LA"))
    )
    (comp (ref "U7")
      (value "TMC2130-LA")
      (footprint "QFN50P500X600X90_HS-37N")
      (description "Stepper Driver IC")
      (libsource (lib "picoprint_library") (part "TMC2130_LA"))
    )
    (comp (ref "U8")
      (value "TMC2130-LA")
      (footprint "QFN50P500X600X90_HS-37N")
      (description "Stepper Driver IC")
      (libsource (lib "picoprint_library") (part "TMC2130_LA"))
    )
    (comp (ref "U9")
      (value "TMC2130-LA")
      (footprint "QFN50P500X600X90_HS-37N")
      (description "Stepper Driver IC")
      (libsource (lib "picoprint_library") (part "TMC2130_LA"))
    )
  )
  (nets
    (net (code "1") (name "+3V3") (class "Default")
      (node (ref "C45") (pin "2") (pinfunction "2_2") (pintype "passive"))
      (node (ref "C49") (pin "2") (pinfunction "2_2") (pintype "passive"))
      (node (ref "C53") (pin "2") (pinfunction "2_2") (pintype "passive"))
      (node (ref "C85") (pin "2") (pinfunction "2_2") (pintype "passive"))
      (node (ref "C89") (pin "2") (pinfunction "2_2") (pintype "passive"))
      (node (ref "U5") (pin "8") (pinfunction "VCC_IO_8") (pintype "power_in"))
      (node (ref "U6") (pin "8") (pinfunction "VCC_IO_8") (pintype "power_in"))
      (node (ref "U7") (pin "8") (pinfunction "VCC_IO_8") (pintype "power_in"))
      (node (ref "U8") (pin "8") (pinfunction "VCC_IO_8") (pintype "power_in"))
      (node (ref "U9") (pin "8") (pinfunction "VCC_IO_8") (pintype "power_in"))
    )
    (net (code "2") (name "+5V") (class "Default")
      (node (ref "C46") (pin "2") (pinfunction "2_2") (pintype "passive"))
      (node (ref "C50") (pin "2") (pinfunction "2_2") (pintype "passive"))
      (node (ref "C54") (pin "2") (pinfunction "2_2") (pintype "passive"))
      (node (ref "C86") (pin "2") (pinfunction "2_2") (pintype "passive"))
      (node (ref "C90") (pin "2") (pinfunction "2_2") (pintype "passive"))
      (node (ref "U5") (pin "26") (pinfunction "VCC_26") (pintype "power_in"))
      (node (ref "U6") (pin "26") (pinfunction "VCC_26") (pintype "power_in"))
      (node (ref "U7") (pin "26") (pinfunction "VCC_26") (pintype "power_in"))
      (node (ref "U8") (pin "26") (pinfunction "VCC_26") (pintype "power_in"))
      (node (ref "U9") (pin "26") (pinfunction "VCC_26") (pintype "power_in"))
    )
    (net (code "3") (name "/E0_CS") (class "Default")
      (node (ref "U8") (pin "2") (pinfunction "CSN_CFG3_2") (pintype "input"))
    )
    (net (code "4") (name "/E0_DIAG1") (class "Default")
      (node (ref "U8") (pin "21") (pinfunction "DIAG1_21") (pintype "bidirectional"))
    )
    (net (code "5") (name "/E0_DIR") (class "Default")
      (node (ref "U8") (pin "7") (pinfunction "DIR_7") (pintype "input"))
    )
    (net (code "6") (name "/E0_MOT_1A") (class "Default")
      (node (ref "C98") (pin "2") (pinfunction "2_2") (pintype "passive"))
      (node (ref "U8") (pin "32") (pinfunction "OA2_32") (pintype "output"))
    )
    (net (code "7") (name "/E0_MOT_1B") (class "Default")
      (node (ref "C97") (pin "2") (pinfunction "2_2") (pintype "passive"))
      (node (ref "U8") (pin "34") (pinfunction "OA1_34") (pintype "output"))
    )
    (net (code "8") (name "/E0_MOT_2A") (class "Default")
      (node (ref "C104") (pin "1") (pinfunction "1_1") (pintype "passive"))
      (node (ref "U8") (pin "13") (pinfunction "OB1_13") (pintype "output"))
    )
    (net (code "9") (name "/E0_MOT_2B") (class "Default")
      (node (ref "C103") (pin "1") (pinfunction "1_1") (pintype "passive"))
      (node (ref "U8") (pin "15") (pinfunction "OB2_15") (pintype "output"))
    )
    (net (code "10") (name "/E0_STEP") (class "Default")
      (node (ref "U8") (pin "6") (pinfunction "STEP_6") (pintype "input"))
    )
    (net (code "11") (name "/E1_CS") (class "Default")
      (node (ref "U9") (pin "2") (pinfunction "CSN_CFG3_2") (pintype "input"))
    )
    (net (code "12") (name "/E1_DIAG1") (class "Default")
      (node (ref "U9") (pin "21") (pinfunction "DIAG1_21") (pintype "bidirectional"))
    )
    (net (code "13") (name "/E1_DIR") (class "Default")
      (node (ref "U9") (pin "7") (pinfunction "DIR_7") (pintype "input"))
    )
    (net (code "14") (name "/E1_MOT_1A") (class "Default")
      (node (ref "C100") (pin "2") (pinfunction "2_2") (pintype "passive"))
      (node (ref "U9") (pin "32") (pinfunction "OA2_32") (pintype "output"))
    )
    (net (code "15") (name "/E1_MOT_1B") (class "Default")
      (node (ref "C99") (pin "2") (pinfunction "2_2") (pintype "passive"))
      (node (ref "U9") (pin "34") (pinfunction "OA1_34") (pintype "output"))
    )
    (net (code "16") (name "/E1_MOT_2A") (class "Default")
      (node (ref "C106") (pin "1") (pinfunction "1_1") (pintype "passive"))
      (node (ref "U9") (pin "13") (pinfunction "OB1_13") (pintype "output"))
    )
    (net (code "17") (name "/E1_MOT_2B") (class "Default")
      (node (ref "C105") (pin "1") (pinfunction "1_1") (pintype "passive"))
      (node (ref "U9") (pin "15") (pinfunction "OB2_15") (pintype "output"))
    )
    (net (code "18") (name "/E1_STEP") (class "Default")
      (node (ref "U9") (pin "6") (pinfunction "STEP_6") (pintype "input"))
    )
    (net (code "19") (name "/SPI4_MISO") (class "Default")
      (node (ref "U5") (pin "5") (pinfunction "SDO_CFG0_5") (pintype "bidirectional"))
      (node (ref "U6") (pin "5") (pinfunction "SDO_CFG0_5") (pintype "bidirectional"))
      (node (ref "U7") (pin "5") (pinfunction "SDO_CFG0_5") (pintype "bidirectional"))
      (node (ref "U8") (pin "5") (pinfunction "SDO_CFG0_5") (pintype "bidirectional"))
      (node (ref "U9") (pin "5") (pinfunction "SDO_CFG0_5") (pintype "bidirectional"))
    )
    (net (code "20") (name "/SPI4_MOSI") (class "Default")
      (node (ref "U5") (pin "4") (pinfunction "SDI_CFG1_4") (pintype "input"))
      (node (ref "U6") (pin "4") (pinfunction "SDI_CFG1_4") (pintype "input"))
      (node (ref "U7") (pin "4") (pinfunction "SDI_CFG1_4") (pintype "input"))
      (node (ref "U8") (pin "4") (pinfunction "SDI_CFG1_4") (pintype "input"))
      (node (ref "U9") (pin "4") (pinfunction "SDI_CFG1_4") (pintype "input"))
    )
    (net (code "21") (name "/SPI4_SCK") (class "Default")
      (node (ref "U5") (pin "3") (pinfunction "SCK_CFG2_3") (pintype "input"))
      (node (ref "U6") (pin "3") (pinfunction "SCK_CFG2_3") (pintype "input"))
      (node (ref "U7") (pin "3") (pinfunction "SCK_CFG2_3") (pintype "input"))
      (node (ref "U8") (pin "3") (pinfunction "SCK_CFG2_3") (pintype "input"))
      (node (ref "U9") (pin "3") (pinfunction "SCK_CFG2_3") (pintype "input"))
    )
    (net (code "22") (name "/X_CS") (class "Default")
      (node (ref "U5") (pin "2") (pinfunction "CSN_CFG3_2") (pintype "input"))
    )
    (net (code "23") (name "/X_DIAG1") (class "Default")
      (node (ref "U5") (pin "21") (pinfunction "DIAG1_21") (pintype "bidirectional"))
    )
    (net (code "24") (name "/X_DIR") (class "Default")
      (node (ref "U5") (pin "7") (pinfunction "DIR_7") (pintype "input"))
    )
    (net (code "25") (name "/X_MOT_1A") (class "Default")
      (node (ref "C58") (pin "2") (pinfunction "2_2") (pintype "passive"))
      (node (ref "U5") (pin "32") (pinfunction "OA2_32") (pintype "output"))
    )
    (net (code "26") (name "/X_MOT_1B") (class "Default")
      (node (ref "C57") (pin "2") (pinfunction "2_2") (pintype "passive"))
      (node (ref "U5") (pin "34") (pinfunction "OA1_34") (pintype "output"))
    )
    (net (code "27") (name "/X_MOT_2A") (class "Default")
      (node (ref "C67") (pin "1") (pinfunction "1_1") (pintype "passive"))
      (node (ref "U5") (pin "13") (pinfunction "OB1_13") (pintype "output"))
    )
    (net (code "28") (name "/X_MOT_2B") (class "Default")
      (node (ref "C66") (pin "1") (pinfunction "1_1") (pintype "passive"))
      (node (ref "U5") (pin "15") (pinfunction "OB2_15") (pintype "output"))
    )
    (net (code "29") (name "/X_STEP") (class "Default")
      (node (ref "U5") (pin "6") (pinfunction "STEP_6") (pintype "input"))
    )
    (net (code "30") (name "/Y_CS") (class "Default")
      (node (ref "U6") (pin "2") (pinfunction "CSN_CFG3_2") (pintype "input"))
    )
    (net (code "31") (name "/Y_DIAG1") (class "Default")
      (node (ref "U6") (pin "21") (pinfunction "DIAG1_21") (pintype "bidirectional"))
    )
    (net (code "32") (name "/Y_DIR") (class "Default")
      (node (ref "U6") (pin "7") (pinfunction "DIR_7") (pintype "input"))
    )
    (net (code "33") (name "/Y_MOT_1A") (class "Default")
      (node (ref "C60") (pin "2") (pinfunction "2_2") (pintype "passive"))
      (node (ref "U6") (pin "32") (pinfunction "OA2_32") (pintype "output"))
    )
    (net (code "34") (name "/Y_MOT_1B") (class "Default")
      (node (ref "C59") (pin "2") (pinfunction "2_2") (pintype "passive"))
      (node (ref "U6") (pin "34") (pinfunction "OA1_34") (pintype "output"))
    )
    (net (code "35") (name "/Y_MOT_2A") (class "Default")
      (node (ref "C69") (pin "1") (pinfunction "1_1") (pintype "passive"))
      (node (ref "U6") (pin "13") (pinfunction "OB1_13") (pintype "output"))
    )
    (net (code "36") (name "/Y_MOT_2B") (class "Default")
      (node (ref "C68") (pin "1") (pinfunction "1_1") (pintype "passive"))
      (node (ref "U6") (pin "15") (pinfunction "OB2_15") (pintype "output"))
    )
    (net (code "37") (name "/Y_STEP") (class "Default")
      (node (ref "U6") (pin "6") (pinfunction "STEP_6") (pintype "input"))
    )
    (net (code "38") (name "/Z_CS") (class "Default")
      (node (ref "U7") (pin "2") (pinfunction "CSN_CFG3_2") (pintype "input"))
    )
    (net (code "39") (name "/Z_DIAG1") (class "Default")
      (node (ref "U7") (pin "21") (pinfunction "DIAG1_21") (pintype "bidirectional"))
    )
    (net (code "40") (name "/Z_DIR") (class "Default")
      (node (ref "U7") (pin "7") (pinfunction "DIR_7") (pintype "input"))
    )
    (net (code "41") (name "/Z_MOT_1A") (class "Default")
      (node (ref "C62") (pin "2") (pinfunction "2_2") (pintype "passive"))
      (node (ref "U7") (pin "32") (pinfunction "OA2_32") (pintype "output"))
    )
    (net (code "42") (name "/Z_MOT_1B") (class "Default")
      (node (ref "C61") (pin "2") (pinfunction "2_2") (pintype "passive"))
      (node (ref "U7") (pin "34") (pinfunction "OA1_34") (pintype "output"))
    )
    (net (code "43") (name "/Z_MOT_2A") (class "Default")
      (node (ref "C71") (pin "1") (pinfunction "1_1") (pintype "passive"))
      (node (ref "U7") (pin "13") (pinfunction "OB1_13") (pintype "output"))
    )
    (net (code "44") (name "/Z_MOT_2B") (class "Default")
      (node (ref "C70") (pin "1") (pinfunction "1_1") (pintype "passive"))
      (node (ref "U7") (pin "15") (pinfunction "OB2_15") (pintype "output"))
    )
    (net (code "45") (name "/Z_STEP") (class "Default")
      (node (ref "U7") (pin "6") (pinfunction "STEP_6") (pintype "input"))
    )
    (net (code "46") (name "GND") (class "Default")
      (node (ref "C100") (pin "1") (pinfunction "1_1") (pintype "passive"))
      (node (ref "C101") (pin "2") (pinfunction "2_2") (pintype "passive"))
      (node (ref "C102") (pin "2") (pinfunction "2_2") (pintype "passive"))
      (node (ref "C103") (pin "2") (pinfunction "2_2") (pintype "passive"))
      (node (ref "C104") (pin "2") (pinfunction "2_2") (pintype "passive"))
      (node (ref "C105") (pin "2") (pinfunction "2_2") (pintype "passive"))
      (node (ref "C106") (pin "2") (pinfunction "2_2") (pintype "passive"))
      (node (ref "C107") (pin "2") (pinfunction "2_2") (pintype "passive"))
      (node (ref "C108") (pin "2") (pinfunction "2_2") (pintype "passive"))
      (node (ref "C114") (pin "1") (pinfunction "1_1") (pintype "passive"))
      (node (ref "C125") (pin "1") (pinfunction "1_1") (pintype "passive"))
      (node (ref "C126") (pin "1") (pinfunction "1_1") (pintype "passive"))
      (node (ref "C127") (pin "1") (pinfunction "1_1") (pintype "passive"))
      (node (ref "C35") (pin "2") (pinfunction "2_2") (pintype "passive"))
      (node (ref "C36") (pin "2") (pinfunction "2_2") (pintype "passive"))
      (node (ref "C37") (pin "1") (pinfunction "1_1") (pintype "passive"))
      (node (ref "C38") (pin "1") (pinfunction "1_1") (pintype "passive"))
      (node (ref "C39") (pin "2") (pinfunction "2_2") (pintype "passive"))
      (node (ref "C40") (pin "2") (pinfunction "2_2") (pintype "passive"))
      (node (ref "C41") (pin "1") (pinfunction "1_1") (pintype "passive"))
      (node (ref "C42") (pin "2") (pinfunction "2_2") (pintype "passive"))
      (node (ref "C43") (pin "2") (pinfunction "2_2") (pintype "passive"))
      (node (ref "C44") (pin "1") (pinfunction "1_1") (pintype "passive"))
      (node (ref "C45") (pin "1") (pinfunction "1_1") (pintype "passive"))
      (node (ref "C46") (pin "1") (pinfunction "1_1") (pintype "passive"))
      (node (ref "C48") (pin "1") (pinfunction "1_1") (pintype "passive"))
      (node (ref "C49") (pin "1") (pinfunction "1_1") (pintype "passive"))
      (node (ref "C50") (pin "1") (pinfunction "1_1") (pintype "passive"))
      (node (ref "C52") (pin "1") (pinfunction "1_1") (pintype "passive"))
      (node (ref "C53") (pin "1") (pinfunction "1_1") (pintype "passive"))
      (node (ref "C54") (pin "1") (pinfunction "1_1") (pintype "passive"))
      (node (ref "C56") (pin "1") (pinfunction "1_1") (pintype "passive"))
      (node (ref "C57") (pin "1") (pinfunction "1_1") (pintype "passive"))
      (node (ref "C58") (pin "1") (pinfunction "1_1") (pintype "passive"))
      (node (ref "C59") (pin "1") (pinfunction "1_1") (pintype "passive"))
      (node (ref "C60") (pin "1") (pinfunction "1_1") (pintype "passive"))
      (node (ref "C61") (pin "1") (pinfunction "1_1") (pintype "passive"))
      (node (ref "C62") (pin "1") (pinfunction "1_1") (pintype "passive"))
      (node (ref "C63") (pin "2") (pinfunction "2_2") (pintype "passive"))
      (node (ref "C64") (pin "2") (pinfunction "2_2") (pintype "passive"))
      (node (ref "C65") (pin "2") (pinfunction "2_2") (pintype "passive"))
      (node (ref "C66") (pin "2") (pinfunction "2_2") (pintype "passive"))
      (node (ref "C67") (pin "2") (pinfunction "2_2") (pintype "passive"))
      (node (ref "C68") (pin "2") (pinfunction "2_2") (pintype "passive"))
      (node (ref "C69") (pin "2") (pinfunction "2_2") (pintype "passive"))
      (node (ref "C70") (pin "2") (pinfunction "2_2") (pintype "passive"))
      (node (ref "C71") (pin "2") (pinfunction "2_2") (pintype "passive"))
      (node (ref "C72") (pin "2") (pinfunction "2_2") (pintype "passive"))
      (node (ref "C73") (pin "2") (pinfunction "2_2") (pintype "passive"))
      (node (ref "C74") (pin "2") (pinfunction "2_2") (pintype "passive"))
      (node (ref "C79") (pin "2") (pinfunction "2_2") (pintype "passive"))
      (node (ref "C80") (pin "2") (pinfunction "2_2") (pintype "passive"))
      (node (ref "C81") (pin "1") (pinfunction "1_1") (pintype "passive"))
      (node (ref "C82") (pin "2") (pinfunction "2_2") (pintype "passive"))
      (node (ref "C83") (pin "2") (pinfunction "2_2") (pintype "passive"))
      (node (ref "C84") (pin "1") (pinfunction "1_1") (pintype "passive"))
      (node (ref "C85") (pin "1") (pinfunction "1_1") (pintype "passive"))
      (node (ref "C86") (pin "1") (pinfunction "1_1") (pintype "passive"))
      (node (ref "C88") (pin "1") (pinfunction "1_1") (pintype "passive"))
      (node (ref "C89") (pin "1") (pinfunction "1_1") (pintype "passive"))
      (node (ref "C90") (pin "1") (pinfunction "1_1") (pintype "passive"))
      (node (ref "C92") (pin "1") (pinfunction "1_1") (pintype "passive"))
      (node (ref "C93") (pin "2") (pinfunction "2_2") (pintype "passive"))
      (node (ref "C94") (pin "2") (pinfunction "2_2") (pintype "passive"))
      (node (ref "C95") (pin "2") (pinfunction "2_2") (pintype "passive"))
      (node (ref "C96") (pin "2") (pinfunction "2_2") (pintype "passive"))
      (node (ref "C97") (pin "1") (pinfunction "1_1") (pintype "passive"))
      (node (ref "C98") (pin "1") (pinfunction "1_1") (pintype "passive"))
      (node (ref "C99") (pin "1") (pinfunction "1_1") (pintype "passive"))
      (node (ref "R55") (pin "1") (pinfunction "1_1") (pintype "passive"))
      (node (ref "R56") (pin "1") (pinfunction "1_1") (pintype "passive"))
      (node (ref "R57") (pin "1") (pinfunction "1_1") (pintype "passive"))
      (node (ref "R58") (pin "1") (pinfunction "1_1") (pintype "passive"))
      (node (ref "R59") (pin "1") (pinfunction "1_1") (pintype "passive"))
      (node (ref "R60") (pin "1") (pinfunction "1_1") (pintype "passive"))
      (node (ref "R61") (pin "1") (pinfunction "1_1") (pintype "passive"))
      (node (ref "R62") (pin "1") (pinfunction "1_1") (pintype "passive"))
      (node (ref "R63") (pin "1") (pinfunction "1_1") (pintype "passive"))
      (node (ref "R64") (pin "1") (pinfunction "1_1") (pintype "passive"))
      (node (ref "U5") (pin "1") (pinfunction "CLK_1") (pintype "input"))
      (node (ref "U5") (pin "11") (pinfunction "NC_11") (pintype "power_in"))
      (node (ref "U5") (pin "12") (pinfunction "GNDP_12") (pintype "power_in"))
      (node (ref "U5") (pin "18") (pinfunction "DCEN_CFG4_18") (pintype "input"))
      (node (ref "U5") (pin "22") (pinfunction "DRV_ENN_CFG6_22") (pintype "input"))
      (node (ref "U5") (pin "24") (pinfunction "GNDA_24") (pintype "power_in"))
      (node (ref "U5") (pin "35") (pinfunction "GNDP_35") (pintype "power_in"))
      (node (ref "U5") (pin "36") (pinfunction "TST_MODE_36") (pintype "input"))
      (node (ref "U5") (pin "37") (pinfunction "DIE_PAD_37") (pintype "power_in"))
      (node (ref "U6") (pin "1") (pinfunction "CLK_1") (pintype "input"))
      (node (ref "U6") (pin "11") (pinfunction "NC_11") (pintype "power_in"))
      (node (ref "U6") (pin "12") (pinfunction "GNDP_12") (pintype "power_in"))
      (node (ref "U6") (pin "18") (pinfunction "DCEN_CFG4_18") (pintype "input"))
      (node (ref "U6") (pin "22") (pinfunction "DRV_ENN_CFG6_22") (pintype "input"))
      (node (ref "U6") (pin "24") (pinfunction "GNDA_24") (pintype "power_in"))
      (node (ref "U6") (pin "35") (pinfunction "GNDP_35") (pintype "power_in"))
      (node (ref "U6") (pin "36") (pinfunction "TST_MODE_36") (pintype "input"))
      (node (ref "U6") (pin "37") (pinfunction "DIE_PAD_37") (pintype "power_in"))
      (node (ref "U7") (pin "1") (pinfunction "CLK_1") (pintype "input"))
      (node (ref "U7") (pin "11") (pinfunction "NC_11") (pintype "power_in"))
      (node (ref "U7") (pin "12") (pinfunction "GNDP_12") (pintype "power_in"))
      (node (ref "U7") (pin "18") (pinfunction "DCEN_CFG4_18") (pintype "input"))
      (node (ref "U7") (pin "22") (pinfunction "DRV_ENN_CFG6_22") (pintype "input"))
      (node (ref "U7") (pin "24") (pinfunction "GNDA_24") (pintype "power_in"))
      (node (ref "U7") (pin "35") (pinfunction "GNDP_35") (pintype "power_in"))
      (node (ref "U7") (pin "36") (pinfunction "TST_MODE_36") (pintype "input"))
      (node (ref "U7") (pin "37") (pinfunction "DIE_PAD_37") (pintype "power_in"))
      (node (ref "U8") (pin "1") (pinfunction "CLK_1") (pintype "input"))
      (node (ref "U8") (pin "11") (pinfunction "NC_11") (pintype "power_in"))
      (node (ref "U8") (pin "12") (pinfunction "GNDP_12") (pintype "power_in"))
      (node (ref "U8") (pin "18") (pinfunction "DCEN_CFG4_18") (pintype "input"))
      (node (ref "U8") (pin "22") (pinfunction "DRV_ENN_CFG6_22") (pintype "input"))
      (node (ref "U8") (pin "24") (pinfunction "GNDA_24") (pintype "power_in"))
      (node (ref "U8") (pin "35") (pinfunction "GNDP_35") (pintype "power_in"))
      (node (ref "U8") (pin "36") (pinfunction "TST_MODE_36") (pintype "input"))
      (node (ref "U8") (pin "37") (pinfunction "DIE_PAD_37") (pintype "power_in"))
      (node (ref "U9") (pin "1") (pinfunction "CLK_1") (pintype "input"))
      (node (ref "U9") (pin "11") (pinfunction "NC_11") (pintype "power_in"))
      (node (ref "U9") (pin "12") (pinfunction "GNDP_12") (pintype "power_in"))
      (node (ref "U9") (pin "18") (pinfunction "DCEN_CFG4_18") (pintype "input"))
      (node (ref "U9") (pin "22") (pinfunction "DRV_ENN_CFG6_22") (pintype "input"))
      (node (ref "U9") (pin "24") (pinfunction "GNDA_24") (pintype "power_in"))
      (node (ref "U9") (pin "35") (pinfunction "GNDP_35") (pintype "power_in"))
      (node (ref "U9") (pin "36") (pinfunction "TST_MODE_36") (pintype "input"))
      (node (ref "U9") (pin "37") (pinfunction "DIE_PAD_37") (pintype "power_in"))
    )
    (net (code "47") (name "Net-(U5-5VOUT)") (class "Default")
      (node (ref "C48") (pin "2") (pinfunction "2_2") (pintype "passive"))
      (node (ref "U5") (pin "25") (pinfunction "5VOUT_25") (pintype "power_in"))
    )
    (net (code "48") (name "Net-(U5-BRA)") (class "Default")
      (node (ref "C63") (pin "1") (pinfunction "1_1") (pintype "passive"))
      (node (ref "R55") (pin "2") (pinfunction "2_2") (pintype "passive"))
      (node (ref "U5") (pin "33") (pinfunction "BRA_33") (pintype "input"))
    )
    (net (code "49") (name "Net-(U5-BRB)") (class "Default")
      (node (ref "C72") (pin "1") (pinfunction "1_1") (pintype "passive"))
      (node (ref "R58") (pin "2") (pinfunction "2_2") (pintype "passive"))
      (node (ref "U5") (pin "14") (pinfunction "BRB_14") (pintype "input"))
    )
    (net (code "50") (name "Net-(U5-CPI)") (class "Default")
      (node (ref "C29") (pin "2") (pinfunction "2_2") (pintype "passive"))
      (node (ref "U5") (pin "28") (pinfunction "CPI_28") (pintype "power_in"))
    )
    (net (code "51") (name "Net-(U5-CPO)") (class "Default")
      (node (ref "C29") (pin "1") (pinfunction "1_1") (pintype "passive"))
      (node (ref "U5") (pin "27") (pinfunction "CPO_27") (pintype "power_in"))
    )
    (net (code "52") (name "Net-(U5-VCP)") (class "Default")
      (node (ref "C30") (pin "2") (pinfunction "2_2") (pintype "passive"))
      (node (ref "U5") (pin "29") (pinfunction "VCP_29") (pintype "power_in"))
    )
    (net (code "53") (name "Net-(U6-5VOUT)") (class "Default")
      (node (ref "C52") (pin "2") (pinfunction "2_2") (pintype "passive"))
      (node (ref "U6") (pin "25") (pinfunction "5VOUT_25") (pintype "power_in"))
    )
    (net (code "54") (name "Net-(U6-BRA)") (class "Default")
      (node (ref "C64") (pin "1") (pinfunction "1_1") (pintype "passive"))
      (node (ref "R56") (pin "2") (pinfunction "2_2") (pintype "passive"))
      (node (ref "U6") (pin "33") (pinfunction "BRA_33") (pintype "input"))
    )
    (net (code "55") (name "Net-(U6-BRB)") (class "Default")
      (node (ref "C73") (pin "1") (pinfunction "1_1") (pintype "passive"))
      (node (ref "R59") (pin "2") (pinfunction "2_2") (pintype "passive"))
      (node (ref "U6") (pin "14") (pinfunction "BRB_14") (pintype "input"))
    )
    (net (code "56") (name "Net-(U6-CPI)") (class "Default")
      (node (ref "C31") (pin "2") (pinfunction "2_2") (pintype "passive"))
      (node (ref "U6") (pin "28") (pinfunction "CPI_28") (pintype "power_in"))
    )
    (net (code "57") (name "Net-(U6-CPO)") (class "Default")
      (node (ref "C31") (pin "1") (pinfunction "1_1") (pintype "passive"))
      (node (ref "U6") (pin "27") (pinfunction "CPO_27") (pintype "power_in"))
    )
    (net (code "58") (name "Net-(U6-VCP)") (class "Default")
      (node (ref "C32") (pin "2") (pinfunction "2_2") (pintype "passive"))
      (node (ref "U6") (pin "29") (pinfunction "VCP_29") (pintype "power_in"))
    )
    (net (code "59") (name "Net-(U7-5VOUT)") (class "Default")
      (node (ref "C56") (pin "2") (pinfunction "2_2") (pintype "passive"))
      (node (ref "U7") (pin "25") (pinfunction "5VOUT_25") (pintype "power_in"))
    )
    (net (code "60") (name "Net-(U7-BRA)") (class "Default")
      (node (ref "C65") (pin "1") (pinfunction "1_1") (pintype "passive"))
      (node (ref "R57") (pin "2") (pinfunction "2_2") (pintype "passive"))
      (node (ref "U7") (pin "33") (pinfunction "BRA_33") (pintype "input"))
    )
    (net (code "61") (name "Net-(U7-BRB)") (class "Default")
      (node (ref "C74") (pin "1") (pinfunction "1_1") (pintype "passive"))
      (node (ref "R60") (pin "2") (pinfunction "2_2") (pintype "passive"))
      (node (ref "U7") (pin "14") (pinfunction "BRB_14") (pintype "input"))
    )
    (net (code "62") (name "Net-(U7-CPI)") (class "Default")
      (node (ref "C33") (pin "2") (pinfunction "2_2") (pintype "passive"))
      (node (ref "U7") (pin "28") (pinfunction "CPI_28") (pintype "power_in"))
    )
    (net (code "63") (name "Net-(U7-CPO)") (class "Default")
      (node (ref "C33") (pin "1") (pinfunction "1_1") (pintype "passive"))
      (node (ref "U7") (pin "27") (pinfunction "CPO_27") (pintype "power_in"))
    )
    (net (code "64") (name "Net-(U7-VCP)") (class "Default")
      (node (ref "C34") (pin "2") (pinfunction "2_2") (pintype "passive"))
      (node (ref "U7") (pin "29") (pinfunction "VCP_29") (pintype "power_in"))
    )
    (net (code "65") (name "Net-(U8-5VOUT)") (class "Default")
      (node (ref "C88") (pin "2") (pinfunction "2_2") (pintype "passive"))
      (node (ref "U8") (pin "25") (pinfunction "5VOUT_25") (pintype "power_in"))
    )
    (net (code "66") (name "Net-(U8-BRA)") (class "Default")
      (node (ref "C101") (pin "1") (pinfunction "1_1") (pintype "passive"))
      (node (ref "R61") (pin "2") (pinfunction "2_2") (pintype "passive"))
      (node (ref "U8") (pin "33") (pinfunction "BRA_33") (pintype "input"))
    )
    (net (code "67") (name "Net-(U8-BRB)") (class "Default")
      (node (ref "C107") (pin "1") (pinfunction "1_1") (pintype "passive"))
      (node (ref "R63") (pin "2") (pinfunction "2_2") (pintype "passive"))
      (node (ref "U8") (pin "14") (pinfunction "BRB_14") (pintype "input"))
    )
    (net (code "68") (name "Net-(U8-CPI)") (class "Default")
      (node (ref "C75") (pin "2") (pinfunction "2_2") (pintype "passive"))
      (node (ref "U8") (pin "28") (pinfunction "CPI_28") (pintype "power_in"))
    )
    (net (code "69") (name "Net-(U8-CPO)") (class "Default")
      (node (ref "C75") (pin "1") (pinfunction "1_1") (pintype "passive"))
      (node (ref "U8") (pin "27") (pinfunction "CPO_27") (pintype "power_in"))
    )
    (net (code "70") (name "Net-(U8-VCP)") (class "Default")
      (node (ref "C76") (pin "2") (pinfunction "2_2") (pintype "passive"))
      (node (ref "U8") (pin "29") (pinfunction "VCP_29") (pintype "power_in"))
    )
    (net (code "71") (name "Net-(U9-5VOUT)") (class "Default")
      (node (ref "C92") (pin "2") (pinfunction "2_2") (pintype "passive"))
      (node (ref "U9") (pin "25") (pinfunction "5VOUT_25") (pintype "power_in"))
    )
    (net (code "72") (name "Net-(U9-BRA)") (class "Default")
      (node (ref "C102") (pin "1") (pinfunction "1_1") (pintype "passive"))
      (node (ref "R62") (pin "2") (pinfunction "2_2") (pintype "passive"))
      (node (ref "U9") (pin "33") (pinfunction "BRA_33") (pintype "input"))
    )
    (net (code "73") (name "Net-(U9-BRB)") (class "Default")
      (node (ref "C108") (pin "1") (pinfunction "1_1") (pintype "passive"))
      (node (ref "R64") (pin "2") (pinfunction "2_2") (pintype "passive"))
      (node (ref "U9") (pin "14") (pinfunction "BRB_14") (pintype "input"))
    )
    (net (code "74") (name "Net-(U9-CPI)") (class "Default")
      (node (ref "C77") (pin "2") (pinfunction "2_2") (pintype "passive"))
      (node (ref "U9") (pin "28") (pinfunction "CPI_28") (pintype "power_in"))
    )
    (net (code "75") (name "Net-(U9-CPO)") (class "Default")
      (node (ref "C77") (pin "1") (pinfunction "1_1") (pintype "passive"))
      (node (ref "U9") (pin "27") (pinfunction "CPO_27") (pintype "power_in"))
    )
    (net (code "76") (name "Net-(U9-VCP)") (class "Default")
      (node (ref "C78") (pin "2") (pinfunction "2_2") (pintype "passive"))
      (node (ref "U9") (pin "29") (pinfunction "VCP_29") (pintype "power_in"))
    )
    (net (code "77") (name "V_MOT") (class "Default")
      (node (ref "C114") (pin "2") (pinfunction "2_2") (pintype "passive"))
      (node (ref "C125") (pin "2") (pinfunction "2_2") (pintype "passive"))
      (node (ref "C126") (pin "2") (pinfunction "2_2") (pintype "passive"))
      (node (ref "C127") (pin "2") (pinfunction "2_2") (pintype "passive"))
      (node (ref "C30") (pin "1") (pinfunction "1_1") (pintype "passive"))
      (node (ref "C32") (pin "1") (pinfunction "1_1") (pintype "passive"))
      (node (ref "C34") (pin "1") (pinfunction "1_1") (pintype "passive"))
      (node (ref "C35") (pin "1") (pinfunction "1_1") (pintype "passive"))
      (node (ref "C36") (pin "1") (pinfunction "1_1") (pintype "passive"))
      (node (ref "C37") (pin "2") (pinfunction "2_2") (pintype "passive"))
      (node (ref "C38") (pin "2") (pinfunction "2_2") (pintype "passive"))
      (node (ref "C39") (pin "1") (pinfunction "1_1") (pintype "passive"))
      (node (ref "C40") (pin "1") (pinfunction "1_1") (pintype "passive"))
      (node (ref "C41") (pin "2") (pinfunction "2_2") (pintype "passive"))
      (node (ref "C42") (pin "1") (pinfunction "1_1") (pintype "passive"))
      (node (ref "C43") (pin "1") (pinfunction "1_1") (pintype "passive"))
      (node (ref "C44") (pin "2") (pinfunction "2_2") (pintype "passive"))
      (node (ref "C76") (pin "1") (pinfunction "1_1") (pintype "passive"))
      (node (ref "C78") (pin "1") (pinfunction "1_1") (pintype "passive"))
      (node (ref "C79") (pin "1") (pinfunction "1_1") (pintype "passive"))
      (node (ref "C80") (pin "1") (pinfunction "1_1") (pintype "passive"))
      (node (ref "C81") (pin "2") (pinfunction "2_2") (pintype "passive"))
      (node (ref "C82") (pin "1") (pinfunction "1_1") (pintype "passive"))
      (node (ref "C83") (pin "1") (pinfunction "1_1") (pintype "passive"))
      (node (ref "C84") (pin "2") (pinfunction "2_2") (pintype "passive"))
      (node (ref "C93") (pin "1") (pinfunction "1_1") (pintype "passive"))
      (node (ref "C94") (pin "1") (pinfunction "1_1") (pintype "passive"))
      (node (ref "C95") (pin "1") (pinfunction "1_1") (pintype "passive"))
      (node (ref "C96") (pin "1") (pinfunction "1_1") (pintype "passive"))
      (node (ref "U5") (pin "16") (pinfunction "VS_16") (pintype "power_in"))
      (node (ref "U5") (pin "30") (pinfunction "VSA_30") (pintype "power_in"))
      (node (ref "U5") (pin "31") (pinfunction "VS_31") (pintype "power_in"))
      (node (ref "U6") (pin "16") (pinfunction "VS_16") (pintype "power_in"))
      (node (ref "U6") (pin "30") (pinfunction "VSA_30") (pintype "power_in"))
      (node (ref "U6") (pin "31") (pinfunction "VS_31") (pintype "power_in"))
      (node (ref "U7") (pin "16") (pinfunction "VS_16") (pintype "power_in"))
      (node (ref "U7") (pin "30") (pinfunction "VSA_30") (pintype "power_in"))
      (node (ref "U7") (pin "31") (pinfunction "VS_31") (pintype "power_in"))
      (node (ref "U8") (pin "16") (pinfunction "VS_16") (pintype "power_in"))
      (node (ref "U8") (pin "30") (pinfunction "VSA_30") (pintype "power_in"))
      (node (ref "U8") (pin "31") (pinfunction "VS_31") (pintype "power_in"))
      (node (ref "U9") (pin "16") (pinfunction "VS_16") (pintype "power_in"))
      (node (ref "U9") (pin "30") (pinfunction "VSA_30") (pintype "power_in"))
      (node (ref "U9") (pin "31") (pinfunction "VS_31") (pintype "power_in"))
    )
    (net (code "78") (name "unconnected-(U5-AIN_IREF-Pad23)") (class "Default")
      (node (ref "U5") (pin "23") (pinfunction "AIN_IREF_23") (pintype "input+no_connect"))
    )
    (net (code "79") (name "unconnected-(U5-DCIN_CFG5-Pad19)") (class "Default")
      (node (ref "U5") (pin "19") (pinfunction "DCIN_CFG5_19") (pintype "input+no_connect"))
    )
    (net (code "80") (name "unconnected-(U5-DCO-Pad17)") (class "Default")
      (node (ref "U5") (pin "17") (pinfunction "DCO_17") (pintype "bidirectional+no_connect"))
    )
    (net (code "81") (name "unconnected-(U5-DIAG0-Pad20)") (class "Default")
      (node (ref "U5") (pin "20") (pinfunction "DIAG0_20") (pintype "bidirectional+no_connect"))
    )
    (net (code "82") (name "unconnected-(U5-NC-Pad9)") (class "Default")
      (node (ref "U5") (pin "9") (pinfunction "NC_9") (pintype "power_in+no_connect"))
    )
    (net (code "83") (name "unconnected-(U5-SPI_MODE-Pad10)") (class "Default")
      (node (ref "U5") (pin "10") (pinfunction "SPI_MODE_10") (pintype "input+no_connect"))
    )
    (net (code "84") (name "unconnected-(U6-AIN_IREF-Pad23)") (class "Default")
      (node (ref "U6") (pin "23") (pinfunction "AIN_IREF_23") (pintype "input+no_connect"))
    )
    (net (code "85") (name "unconnected-(U6-DCIN_CFG5-Pad19)") (class "Default")
      (node (ref "U6") (pin "19") (pinfunction "DCIN_CFG5_19") (pintype "input+no_connect"))
    )
    (net (code "86") (name "unconnected-(U6-DCO-Pad17)") (class "Default")
      (node (ref "U6") (pin "17") (pinfunction "DCO_17") (pintype "bidirectional+no_connect"))
    )
    (net (code "87") (name "unconnected-(U6-DIAG0-Pad20)") (class "Default")
      (node (ref "U6") (pin "20") (pinfunction "DIAG0_20") (pintype "bidirectional+no_connect"))
    )
    (net (code "88") (name "unconnected-(U6-NC-Pad9)") (class "Default")
      (node (ref "U6") (pin "9") (pinfunction "NC_9") (pintype "power_in+no_connect"))
    )
    (net (code "89") (name "unconnected-(U6-SPI_MODE-Pad10)") (class "Default")
      (node (ref "U6") (pin "10") (pinfunction "SPI_MODE_10") (pintype "input+no_connect"))
    )
    (net (code "90") (name "unconnected-(U7-AIN_IREF-Pad23)") (class "Default")
      (node (ref "U7") (pin "23") (pinfunction "AIN_IREF_23") (pintype "input+no_connect"))
    )
    (net (code "91") (name "unconnected-(U7-DCIN_CFG5-Pad19)") (class "Default")
      (node (ref "U7") (pin "19") (pinfunction "DCIN_CFG5_19") (pintype "input+no_connect"))
    )
    (net (code "92") (name "unconnected-(U7-DCO-Pad17)") (class "Default")
      (node (ref "U7") (pin "17") (pinfunction "DCO_17") (pintype "bidirectional+no_connect"))
    )
    (net (code "93") (name "unconnected-(U7-DIAG0-Pad20)") (class "Default")
      (node (ref "U7") (pin "20") (pinfunction "DIAG0_20") (pintype "bidirectional+no_connect"))
    )
    (net (code "94") (name "unconnected-(U7-NC-Pad9)") (class "Default")
      (node (ref "U7") (pin "9") (pinfunction "NC_9") (pintype "power_in+no_connect"))
    )
    (net (code "95") (name "unconnected-(U7-SPI_MODE-Pad10)") (class "Default")
      (node (ref "U7") (pin "10") (pinfunction "SPI_MODE_10") (pintype "input+no_connect"))
    )
    (net (code "96") (name "unconnected-(U8-AIN_IREF-Pad23)") (class "Default")
      (node (ref "U8") (pin "23") (pinfunction "AIN_IREF_23") (pintype "input+no_connect"))
    )
    (net (code "97") (name "unconnected-(U8-DCIN_CFG5-Pad19)") (class "Default")
      (node (ref "U8") (pin "19") (pinfunction "DCIN_CFG5_19") (pintype "input+no_connect"))
    )
    (net (code "98") (name "unconnected-(U8-DCO-Pad17)") (class "Default")
      (node (ref "U8") (pin "17") (pinfunction "DCO_17") (pintype "bidirectional+no_connect"))
    )
    (net (code "99") (name "unconnected-(U8-DIAG0-Pad20)") (class "Default")
      (node (ref "U8") (pin "20") (pinfunction "DIAG0_20") (pintype "bidirectional+no_connect"))
    )
    (net (code "100") (name "unconnected-(U8-NC-Pad9)") (class "Default")
      (node (ref "U8") (pin "9") (pinfunction "NC_9") (pintype "power_in+no_connect"))
    )
    (net (code "101") (name "unconnected-(U8-SPI_MODE-Pad10)") (class "Default")
      (node (ref "U8") (pin "10") (pinfunction "SPI_MODE_10") (pintype "input+no_connect"))
    )
    (net (code "102") (name "unconnected-(U9-AIN_IREF-Pad23)") (class "Default")
      (node (ref "U9") (pin "23") (pinfunction "AIN_IREF_23") (pintype "input+no_connect"))
    )
    (net (code "103") (name "unconnected-(U9-DCIN_CFG5-Pad19)") (class "Default")
      (node (ref "U9") (pin "19") (pinfunction "DCIN_CFG5_19") (pintype "input+no_connect"))
    )
    (net (code "104") (name "unconnected-(U9-DCO-Pad17)") (class "Default")
      (node (ref "U9") (pin "17") (pinfunction "DCO_17") (pintype "bidirectional+no_connect"))
    )
    (net (code "105") (name "unconnected-(U9-DIAG0-Pad20)") (class "Default")
      (node (ref "U9") (pin "20") (pinfunction "DIAG0_20") (pintype "bidirectional+no_connect"))
    )
    (net (code "106") (name "unconnected-(U9-NC-Pad9)") (class "Default")
      (node (ref "U9") (pin "9") (pinfunction "NC_9") (pintype "power_in+no_connect"))
    )
    (net (code "107") (name "unconnected-(U9-SPI_MODE-Pad10)") (class "Default")
      (node (ref "U9") (pin "10") (pinfunction "SPI_MODE_10") (pintype "input+no_connect"))
    )
  )
)
